# SSR_Control.net
KiCad netlist of a schematic drawn in Altium Designer
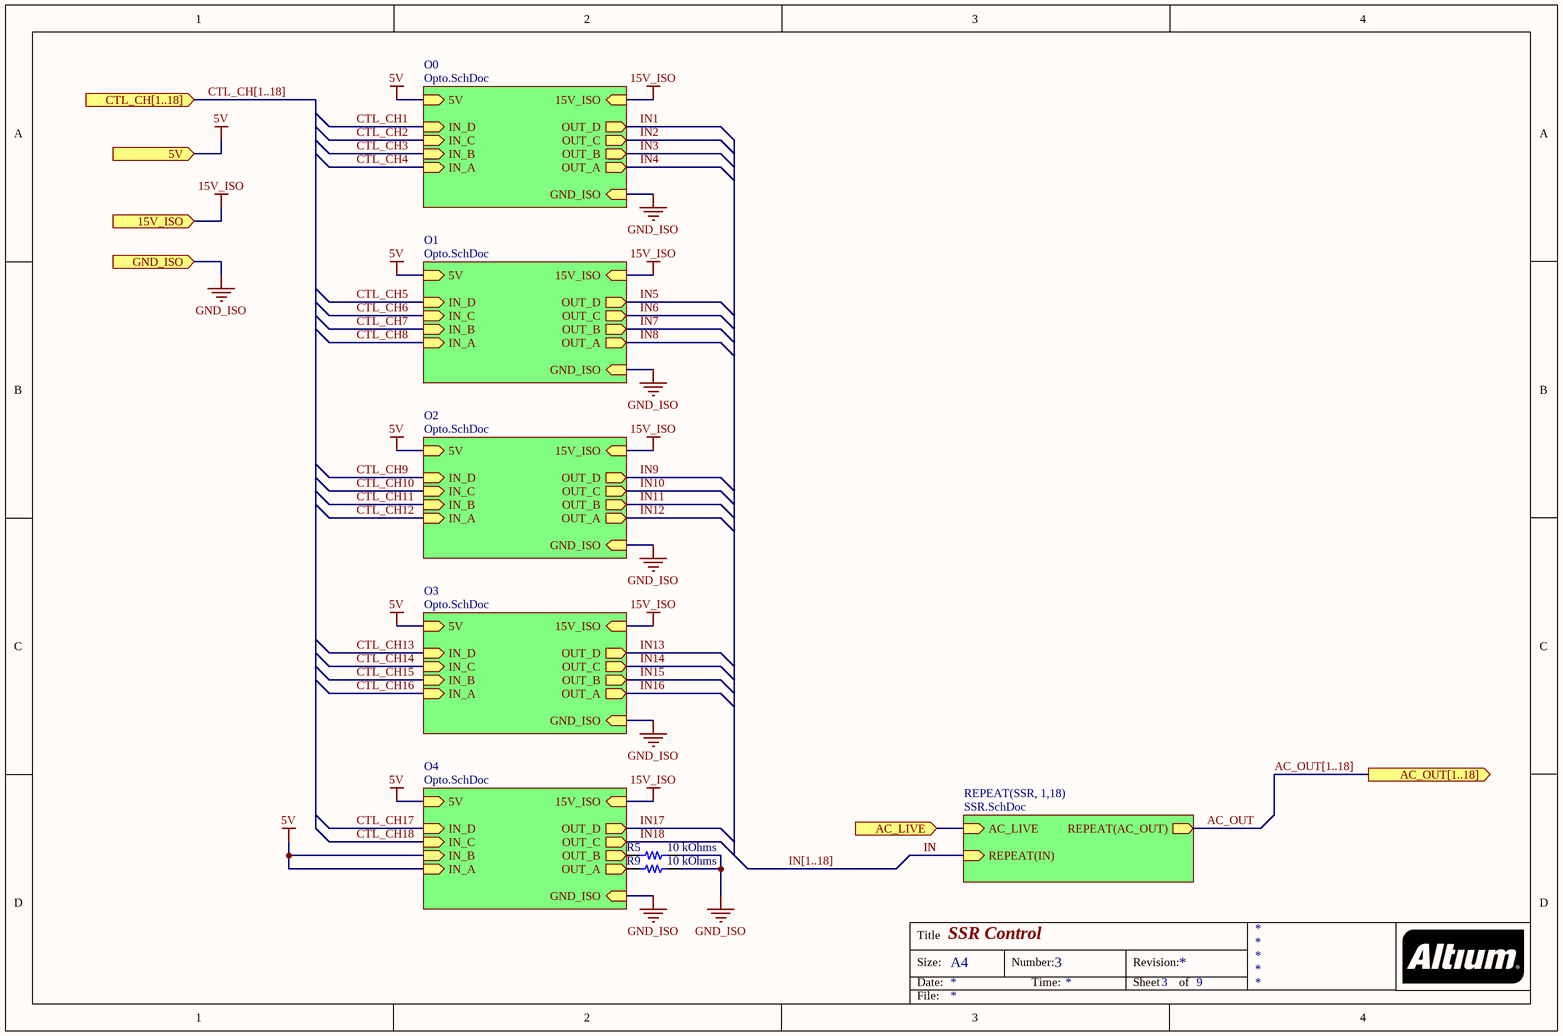
[diagram p0: SSR Control.SchDoc]

(export (version "E")
  (design (tool "Eeschema 10.0.6"))
  (components
    (comp (ref "R5")
      (value "10 kOhms")
      (footprint "RES 0603_1608")
      (description "RES 10K OHM 1% 1/5W 0603")
      (fields
        (field (name "PART NUMBER") "SG73S1JTTD1002F")
        (field (name "MANUFACTURER") "KOA Speer Electronics, Inc.")
      )
      (libsource (lib "altiumlibrary.com") (part "Resistor"))
    )
    (comp (ref "R9")
      (value "10 kOhms")
      (footprint "RES 0603_1608")
      (description "RES 10K OHM 1% 1/5W 0603")
      (fields
        (field (name "PART NUMBER") "SG73S1JTTD1002F")
        (field (name "MANUFACTURER") "KOA Speer Electronics, Inc.")
      )
      (libsource (lib "altiumlibrary.com") (part "Resistor"))
    )
  )
  (nets
    (net (code "61") (name "/OUT_A") (class "Default")
      (node (ref "R9") (pin "1") (pinfunction "1_1") (pintype "passive"))
    )
    (net (code "62") (name "/OUT_B") (class "Default")
      (node (ref "R5") (pin "1") (pinfunction "1_1") (pintype "passive"))
    )
    (net (code "65") (name "GND_ISO") (class "Default")
      (node (ref "R5") (pin "2") (pinfunction "2_2") (pintype "passive"))
      (node (ref "R9") (pin "2") (pinfunction "2_2") (pintype "passive"))
    )
  )
)
